# proto.net
KiCad netlist of a schematic drawn in EAGLE
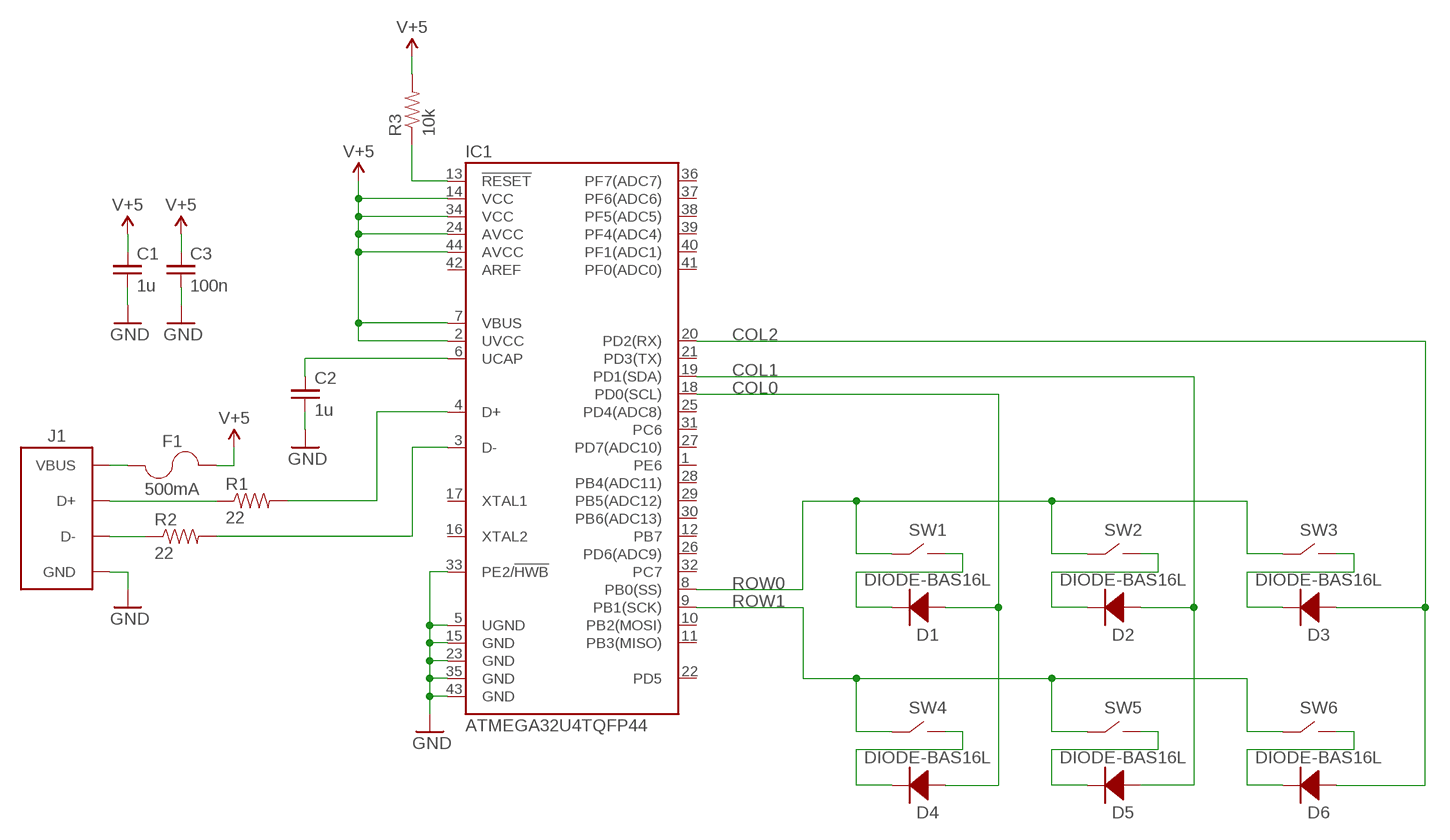
[diagram p0: schematic, sheet 1]

(export (version "E")
  (design (tool "Eeschema 10.0.6"))
  (components
    (comp (ref "C1")
      (value "1u")
      (footprint "eagle-import:0805")
      (libsource (lib "eagle-import") (part "CAP-0805"))
    )
    (comp (ref "C2")
      (value "1u")
      (footprint "eagle-import:0805")
      (libsource (lib "eagle-import") (part "CAP-0805"))
    )
    (comp (ref "C3")
      (value "100n")
      (footprint "eagle-import:0805")
      (libsource (lib "eagle-import") (part "CAP-0805"))
    )
    (comp (ref "D1")
      (value "DIODE-BAS16L")
      (footprint "eagle-import:SOT23-3")
      (libsource (lib "eagle-import") (part "DIODE-BAS16L"))
    )
    (comp (ref "D2")
      (value "DIODE-BAS16L")
      (footprint "eagle-import:SOT23-3")
      (libsource (lib "eagle-import") (part "DIODE-BAS16L"))
    )
    (comp (ref "D3")
      (value "DIODE-BAS16L")
      (footprint "eagle-import:SOT23-3")
      (libsource (lib "eagle-import") (part "DIODE-BAS16L"))
    )
    (comp (ref "D4")
      (value "DIODE-BAS16L")
      (footprint "eagle-import:SOT23-3")
      (libsource (lib "eagle-import") (part "DIODE-BAS16L"))
    )
    (comp (ref "D5")
      (value "DIODE-BAS16L")
      (footprint "eagle-import:SOT23-3")
      (libsource (lib "eagle-import") (part "DIODE-BAS16L"))
    )
    (comp (ref "D6")
      (value "DIODE-BAS16L")
      (footprint "eagle-import:SOT23-3")
      (libsource (lib "eagle-import") (part "DIODE-BAS16L"))
    )
    (comp (ref "F1")
      (value "500mA")
      (footprint "eagle-import:0805")
      (libsource (lib "eagle-import") (part "FUSE"))
    )
    (comp (ref "IC1")
      (value "ATMEGA32U4TQFP44")
      (footprint "eagle-import:QFP80P1200X1225X120-44")
      (libsource (lib "eagle-import") (part "ATMEGA32U4TQFP44"))
    )
    (comp (ref "J1")
      (value "USB2.0-C")
      (footprint "eagle-import:USB-C")
      (libsource (lib "eagle-import") (part "USB2.0-C"))
    )
    (comp (ref "R1")
      (value "22")
      (footprint "eagle-import:0805")
      (libsource (lib "eagle-import") (part "RESISTOR-0805"))
    )
    (comp (ref "R2")
      (value "22")
      (footprint "eagle-import:0805")
      (libsource (lib "eagle-import") (part "RESISTOR-0805"))
    )
    (comp (ref "R3")
      (value "10k")
      (footprint "eagle-import:0805")
      (libsource (lib "eagle-import") (part "RESISTOR-0805"))
    )
    (comp (ref "SW1")
      (value "SWITCH-SPSTCHERRY")
      (footprint "eagle-import:CHERRY-MX")
      (libsource (lib "eagle-import") (part "SWITCH-SPSTCHERRY"))
    )
    (comp (ref "SW2")
      (value "SWITCH-SPSTCHERRY")
      (footprint "eagle-import:CHERRY-MX")
      (libsource (lib "eagle-import") (part "SWITCH-SPSTCHERRY"))
    )
    (comp (ref "SW3")
      (value "SWITCH-SPSTCHERRY")
      (footprint "eagle-import:CHERRY-MX")
      (libsource (lib "eagle-import") (part "SWITCH-SPSTCHERRY"))
    )
    (comp (ref "SW4")
      (value "SWITCH-SPSTCHERRY")
      (footprint "eagle-import:CHERRY-MX")
      (libsource (lib "eagle-import") (part "SWITCH-SPSTCHERRY"))
    )
    (comp (ref "SW5")
      (value "SWITCH-SPSTCHERRY")
      (footprint "eagle-import:CHERRY-MX")
      (libsource (lib "eagle-import") (part "SWITCH-SPSTCHERRY"))
    )
    (comp (ref "SW6")
      (value "SWITCH-SPSTCHERRY")
      (footprint "eagle-import:CHERRY-MX")
      (libsource (lib "eagle-import") (part "SWITCH-SPSTCHERRY"))
    )
  )
  (nets
    (net (code "1") (name "/COL0") (class "Default")
      (node (ref "D1") (pin "1") (pinfunction "ANODE+_1") (pintype "passive"))
      (node (ref "D4") (pin "1") (pinfunction "ANODE+_1") (pintype "passive"))
      (node (ref "IC1") (pin "18") (pinfunction "PD0(SCL)_18") (pintype "bidirectional"))
    )
    (net (code "2") (name "/COL1") (class "Default")
      (node (ref "D2") (pin "1") (pinfunction "ANODE+_1") (pintype "passive"))
      (node (ref "D5") (pin "1") (pinfunction "ANODE+_1") (pintype "passive"))
      (node (ref "IC1") (pin "19") (pinfunction "PD1(SDA)_19") (pintype "bidirectional"))
    )
    (net (code "3") (name "/COL2") (class "Default")
      (node (ref "D3") (pin "1") (pinfunction "ANODE+_1") (pintype "passive"))
      (node (ref "D6") (pin "1") (pinfunction "ANODE+_1") (pintype "passive"))
      (node (ref "IC1") (pin "20") (pinfunction "PD2(RX)_20") (pintype "bidirectional"))
    )
    (net (code "4") (name "/ROW0") (class "Default")
      (node (ref "IC1") (pin "8") (pinfunction "PB0(SS)_8") (pintype "bidirectional"))
      (node (ref "SW1") (pin "P$1") (pinfunction "P$1_P$1") (pintype "passive"))
      (node (ref "SW2") (pin "P$1") (pinfunction "P$1_P$1") (pintype "passive"))
      (node (ref "SW3") (pin "P$1") (pinfunction "P$1_P$1") (pintype "passive"))
    )
    (net (code "5") (name "/ROW1") (class "Default")
      (node (ref "IC1") (pin "9") (pinfunction "PB1(SCK)_9") (pintype "bidirectional"))
      (node (ref "SW4") (pin "P$1") (pinfunction "P$1_P$1") (pintype "passive"))
      (node (ref "SW5") (pin "P$1") (pinfunction "P$1_P$1") (pintype "passive"))
      (node (ref "SW6") (pin "P$1") (pinfunction "P$1_P$1") (pintype "passive"))
    )
    (net (code "6") (name "GND") (class "Default")
      (node (ref "C1") (pin "2") (pinfunction "2_2") (pintype "passive"))
      (node (ref "C2") (pin "2") (pinfunction "2_2") (pintype "passive"))
      (node (ref "C3") (pin "2") (pinfunction "2_2") (pintype "passive"))
      (node (ref "IC1") (pin "15") (pinfunction "GND_15") (pintype "power_in"))
      (node (ref "IC1") (pin "23") (pinfunction "GND_23") (pintype "power_in"))
      (node (ref "IC1") (pin "33") (pinfunction "PE2/~{HWB}_33") (pintype "bidirectional"))
      (node (ref "IC1") (pin "35") (pinfunction "GND_35") (pintype "power_in"))
      (node (ref "IC1") (pin "43") (pinfunction "GND_43") (pintype "power_in"))
      (node (ref "IC1") (pin "5") (pinfunction "UGND_5") (pintype "power_in"))
      (node (ref "J1") (pin "GND@1") (pinfunction "GND_GND@1") (pintype "power_in"))
      (node (ref "J1") (pin "GND@10") (pinfunction "GND_GND@10") (pintype "power_in"))
      (node (ref "J1") (pin "GND@11") (pinfunction "GND_GND@11") (pintype "power_in"))
      (node (ref "J1") (pin "GND@12") (pinfunction "GND_GND@12") (pintype "power_in"))
      (node (ref "J1") (pin "GND@13") (pinfunction "GND_GND@13") (pintype "power_in"))
      (node (ref "J1") (pin "GND@14") (pinfunction "GND_GND@14") (pintype "power_in"))
      (node (ref "J1") (pin "GND@15") (pinfunction "GND_GND@15") (pintype "power_in"))
      (node (ref "J1") (pin "GND@16") (pinfunction "GND_GND@16") (pintype "power_in"))
      (node (ref "J1") (pin "GND@2") (pinfunction "GND_GND@2") (pintype "power_in"))
      (node (ref "J1") (pin "GND@3") (pinfunction "GND_GND@3") (pintype "power_in"))
      (node (ref "J1") (pin "GND@4") (pinfunction "GND_GND@4") (pintype "power_in"))
      (node (ref "J1") (pin "GND@5") (pinfunction "GND_GND@5") (pintype "power_in"))
      (node (ref "J1") (pin "GND@6") (pinfunction "GND_GND@6") (pintype "power_in"))
      (node (ref "J1") (pin "GND@7") (pinfunction "GND_GND@7") (pintype "power_in"))
      (node (ref "J1") (pin "GND@8") (pinfunction "GND_GND@8") (pintype "power_in"))
      (node (ref "J1") (pin "GND@9") (pinfunction "GND_GND@9") (pintype "power_in"))
    )
    (net (code "7") (name "Net-(D1-CATHODE-)") (class "Default")
      (node (ref "D1") (pin "3") (pinfunction "CATHODE-_3") (pintype "passive"))
      (node (ref "SW1") (pin "P$2") (pinfunction "P$2_P$2") (pintype "passive"))
    )
    (net (code "8") (name "Net-(D2-CATHODE-)") (class "Default")
      (node (ref "D2") (pin "3") (pinfunction "CATHODE-_3") (pintype "passive"))
      (node (ref "SW2") (pin "P$2") (pinfunction "P$2_P$2") (pintype "passive"))
    )
    (net (code "9") (name "Net-(D3-CATHODE-)") (class "Default")
      (node (ref "D3") (pin "3") (pinfunction "CATHODE-_3") (pintype "passive"))
      (node (ref "SW3") (pin "P$2") (pinfunction "P$2_P$2") (pintype "passive"))
    )
    (net (code "10") (name "Net-(D4-CATHODE-)") (class "Default")
      (node (ref "D4") (pin "3") (pinfunction "CATHODE-_3") (pintype "passive"))
      (node (ref "SW4") (pin "P$2") (pinfunction "P$2_P$2") (pintype "passive"))
    )
    (net (code "11") (name "Net-(D5-CATHODE-)") (class "Default")
      (node (ref "D5") (pin "3") (pinfunction "CATHODE-_3") (pintype "passive"))
      (node (ref "SW5") (pin "P$2") (pinfunction "P$2_P$2") (pintype "passive"))
    )
    (net (code "12") (name "Net-(D6-CATHODE-)") (class "Default")
      (node (ref "D6") (pin "3") (pinfunction "CATHODE-_3") (pintype "passive"))
      (node (ref "SW6") (pin "P$2") (pinfunction "P$2_P$2") (pintype "passive"))
    )
    (net (code "13") (name "Net-(F1-Pad1)") (class "Default")
      (node (ref "F1") (pin "1") (pinfunction "1_1") (pintype "passive"))
      (node (ref "J1") (pin "VBUS@1") (pinfunction "VBUS_VBUS@1") (pintype "power_in"))
      (node (ref "J1") (pin "VBUS@2") (pinfunction "VBUS_VBUS@2") (pintype "power_in"))
      (node (ref "J1") (pin "VBUS@3") (pinfunction "VBUS_VBUS@3") (pintype "power_in"))
      (node (ref "J1") (pin "VBUS@4") (pinfunction "VBUS_VBUS@4") (pintype "power_in"))
    )
    (net (code "14") (name "Net-(IC1-D+)") (class "Default")
      (node (ref "IC1") (pin "4") (pinfunction "D+_4") (pintype "bidirectional"))
      (node (ref "R1") (pin "2") (pinfunction "2_2") (pintype "passive"))
    )
    (net (code "15") (name "Net-(IC1-D-)") (class "Default")
      (node (ref "IC1") (pin "3") (pinfunction "D-_3") (pintype "bidirectional"))
      (node (ref "R2") (pin "2") (pinfunction "2_2") (pintype "passive"))
    )
    (net (code "16") (name "Net-(IC1-UCAP)") (class "Default")
      (node (ref "C2") (pin "1") (pinfunction "1_1") (pintype "passive"))
      (node (ref "IC1") (pin "6") (pinfunction "UCAP_6") (pintype "power_in"))
    )
    (net (code "17") (name "Net-(IC1-~{RESET})") (class "Default")
      (node (ref "IC1") (pin "13") (pinfunction "~{RESET}_13") (pintype "input"))
      (node (ref "R3") (pin "1") (pinfunction "1_1") (pintype "passive"))
    )
    (net (code "18") (name "Net-(J1-D+-PadD+@1)") (class "Default")
      (node (ref "J1") (pin "D+@1") (pinfunction "D+_D+@1") (pintype "bidirectional"))
      (node (ref "J1") (pin "D+@2") (pinfunction "D+_D+@2") (pintype "bidirectional"))
      (node (ref "R1") (pin "1") (pinfunction "1_1") (pintype "passive"))
    )
    (net (code "19") (name "Net-(J1-D--PadD-@1)") (class "Default")
      (node (ref "J1") (pin "D-@1") (pinfunction "D-_D-@1") (pintype "bidirectional"))
      (node (ref "J1") (pin "D-@2") (pinfunction "D-_D-@2") (pintype "bidirectional"))
      (node (ref "R2") (pin "1") (pinfunction "1_1") (pintype "passive"))
    )
    (net (code "20") (name "V+5") (class "Default")
      (node (ref "C1") (pin "1") (pinfunction "1_1") (pintype "passive"))
      (node (ref "C3") (pin "1") (pinfunction "1_1") (pintype "passive"))
      (node (ref "F1") (pin "2") (pinfunction "2_2") (pintype "passive"))
      (node (ref "IC1") (pin "14") (pinfunction "VCC_14") (pintype "power_in"))
      (node (ref "IC1") (pin "2") (pinfunction "UVCC_2") (pintype "power_in"))
      (node (ref "IC1") (pin "24") (pinfunction "AVCC_24") (pintype "power_in"))
      (node (ref "IC1") (pin "34") (pinfunction "VCC_34") (pintype "power_in"))
      (node (ref "IC1") (pin "44") (pinfunction "AVCC_44") (pintype "power_in"))
      (node (ref "IC1") (pin "7") (pinfunction "VBUS_7") (pintype "input"))
      (node (ref "R3") (pin "2") (pinfunction "2_2") (pintype "passive"))
    )
    (net (code "21") (name "unconnected-(IC1-AREF-Pad42)") (class "Default")
      (node (ref "IC1") (pin "42") (pinfunction "AREF_42") (pintype "output"))
    )
    (net (code "22") (name "unconnected-(IC1-PB2(MOSI)-Pad10)") (class "Default")
      (node (ref "IC1") (pin "10") (pinfunction "PB2(MOSI)_10") (pintype "bidirectional"))
    )
    (net (code "23") (name "unconnected-(IC1-PB3(MISO)-Pad11)") (class "Default")
      (node (ref "IC1") (pin "11") (pinfunction "PB3(MISO)_11") (pintype "bidirectional"))
    )
    (net (code "24") (name "unconnected-(IC1-PB4(ADC11)-Pad28)") (class "Default")
      (node (ref "IC1") (pin "28") (pinfunction "PB4(ADC11)_28") (pintype "bidirectional"))
    )
    (net (code "25") (name "unconnected-(IC1-PB5(ADC12)-Pad29)") (class "Default")
      (node (ref "IC1") (pin "29") (pinfunction "PB5(ADC12)_29") (pintype "bidirectional"))
    )
    (net (code "26") (name "unconnected-(IC1-PB6(ADC13)-Pad30)") (class "Default")
      (node (ref "IC1") (pin "30") (pinfunction "PB6(ADC13)_30") (pintype "bidirectional"))
    )
    (net (code "27") (name "unconnected-(IC1-PB7-Pad12)") (class "Default")
      (node (ref "IC1") (pin "12") (pinfunction "PB7_12") (pintype "bidirectional"))
    )
    (net (code "28") (name "unconnected-(IC1-PC6-Pad31)") (class "Default")
      (node (ref "IC1") (pin "31") (pinfunction "PC6_31") (pintype "bidirectional"))
    )
    (net (code "29") (name "unconnected-(IC1-PC7-Pad32)") (class "Default")
      (node (ref "IC1") (pin "32") (pinfunction "PC7_32") (pintype "bidirectional"))
    )
    (net (code "30") (name "unconnected-(IC1-PD3(TX)-Pad21)") (class "Default")
      (node (ref "IC1") (pin "21") (pinfunction "PD3(TX)_21") (pintype "bidirectional"))
    )
    (net (code "31") (name "unconnected-(IC1-PD4(ADC8)-Pad25)") (class "Default")
      (node (ref "IC1") (pin "25") (pinfunction "PD4(ADC8)_25") (pintype "bidirectional"))
    )
    (net (code "32") (name "unconnected-(IC1-PD5-Pad22)") (class "Default")
      (node (ref "IC1") (pin "22") (pinfunction "PD5_22") (pintype "bidirectional"))
    )
    (net (code "33") (name "unconnected-(IC1-PD6(ADC9)-Pad26)") (class "Default")
      (node (ref "IC1") (pin "26") (pinfunction "PD6(ADC9)_26") (pintype "bidirectional"))
    )
    (net (code "34") (name "unconnected-(IC1-PD7(ADC10)-Pad27)") (class "Default")
      (node (ref "IC1") (pin "27") (pinfunction "PD7(ADC10)_27") (pintype "bidirectional"))
    )
    (net (code "35") (name "unconnected-(IC1-PE6-Pad1)") (class "Default")
      (node (ref "IC1") (pin "1") (pinfunction "PE6_1") (pintype "bidirectional"))
    )
    (net (code "36") (name "unconnected-(IC1-PF0(ADC0)-Pad41)") (class "Default")
      (node (ref "IC1") (pin "41") (pinfunction "PF0(ADC0)_41") (pintype "bidirectional"))
    )
    (net (code "37") (name "unconnected-(IC1-PF1(ADC1)-Pad40)") (class "Default")
      (node (ref "IC1") (pin "40") (pinfunction "PF1(ADC1)_40") (pintype "bidirectional"))
    )
    (net (code "38") (name "unconnected-(IC1-PF4(ADC4)-Pad39)") (class "Default")
      (node (ref "IC1") (pin "39") (pinfunction "PF4(ADC4)_39") (pintype "bidirectional"))
    )
    (net (code "39") (name "unconnected-(IC1-PF5(ADC5)-Pad38)") (class "Default")
      (node (ref "IC1") (pin "38") (pinfunction "PF5(ADC5)_38") (pintype "bidirectional"))
    )
    (net (code "40") (name "unconnected-(IC1-PF6(ADC6)-Pad37)") (class "Default")
      (node (ref "IC1") (pin "37") (pinfunction "PF6(ADC6)_37") (pintype "bidirectional"))
    )
    (net (code "41") (name "unconnected-(IC1-PF7(ADC7)-Pad36)") (class "Default")
      (node (ref "IC1") (pin "36") (pinfunction "PF7(ADC7)_36") (pintype "bidirectional"))
    )
    (net (code "42") (name "unconnected-(IC1-XTAL1-Pad17)") (class "Default")
      (node (ref "IC1") (pin "17") (pinfunction "XTAL1_17") (pintype "bidirectional"))
    )
    (net (code "43") (name "unconnected-(IC1-XTAL2-Pad16)") (class "Default")
      (node (ref "IC1") (pin "16") (pinfunction "XTAL2_16") (pintype "bidirectional"))
    )
  )
)
